# esp_console.net
KiCad netlist of a schematic drawn in EAGLE
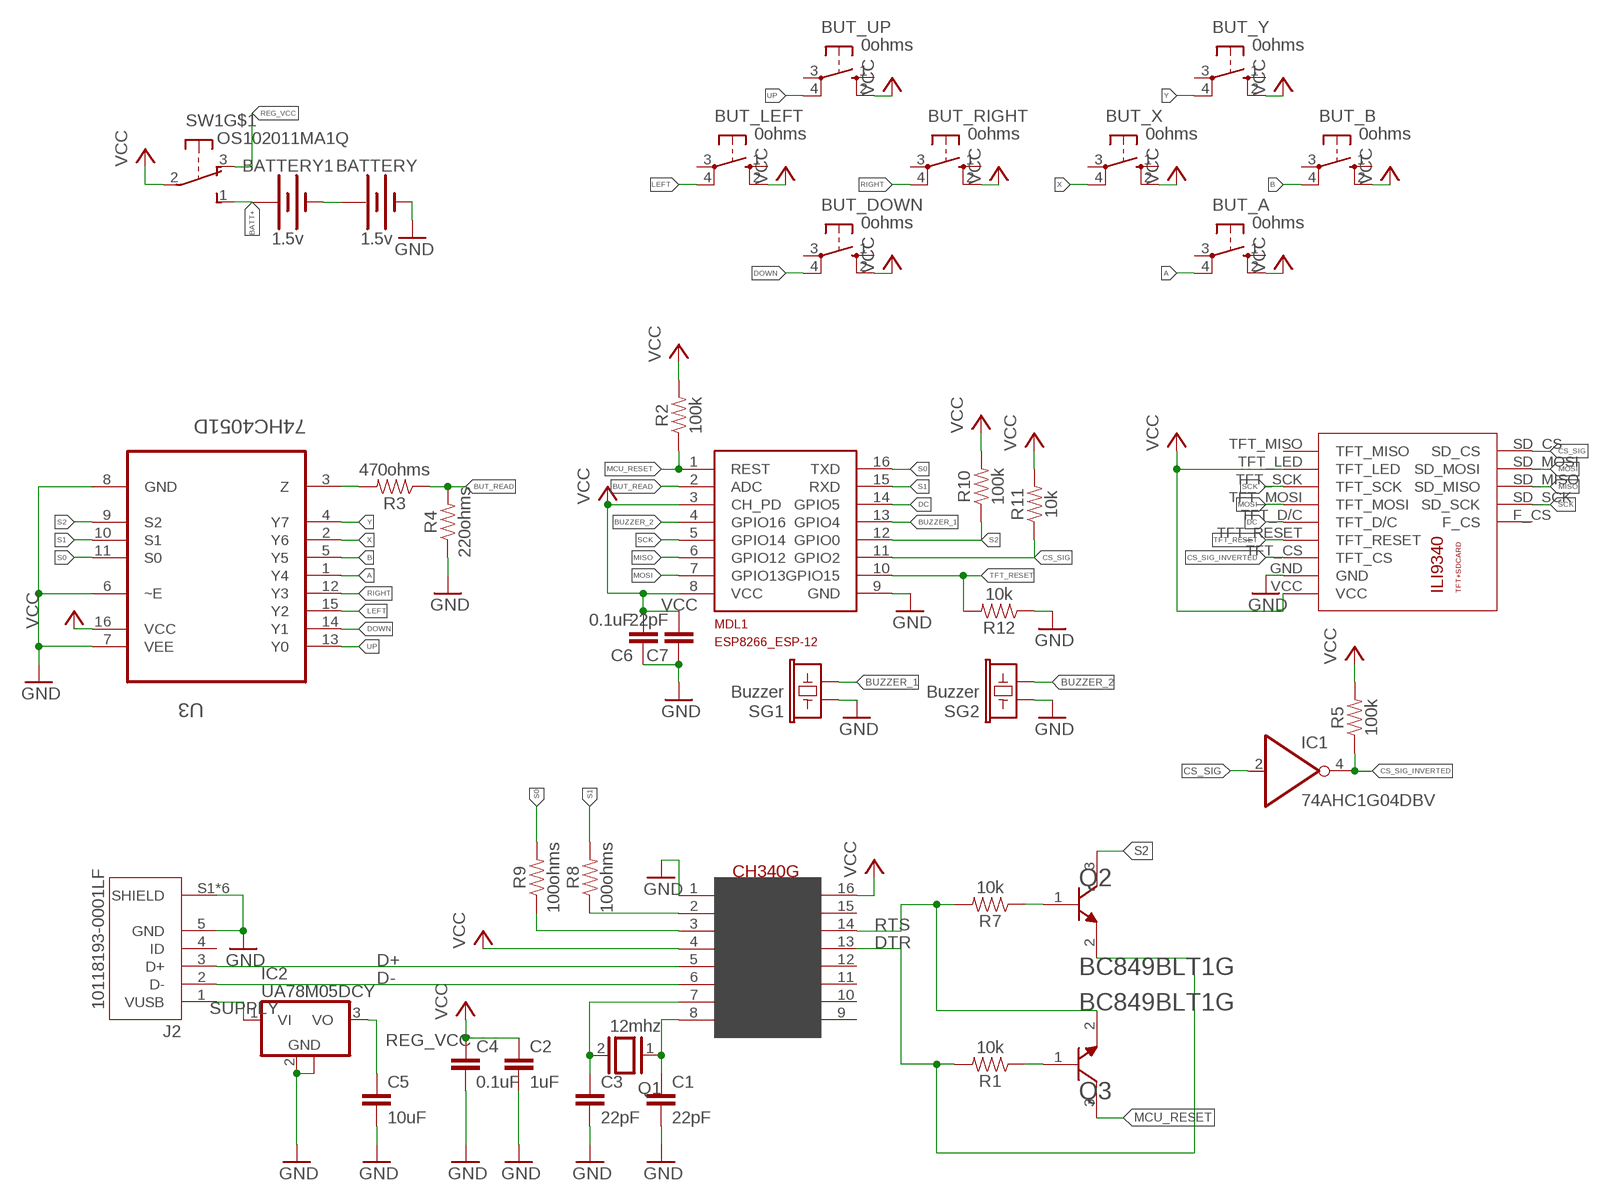
[diagram p0: schematic, sheet 1]

(export (version "E")
  (design (tool "Eeschema 10.0.6"))
  (components
    (comp (ref "BATTERY")
      (value "1.5v")
      (footprint "eagle-import:BATTERY-AA")
      (libsource (lib "eagle-import") (part "BATTERY-AA"))
    )
    (comp (ref "BATTERY1")
      (value "1.5v")
      (footprint "eagle-import:BATTERY-AA")
      (libsource (lib "eagle-import") (part "BATTERY-AA"))
    )
    (comp (ref "BUT_A")
      (value "0ohms")
      (footprint "eagle-import:B3F-10XX")
      (fields (field (name "MPN") "B3F-1000"))
      (libsource (lib "eagle-import") (part "10-XX"))
    )
    (comp (ref "BUT_B")
      (value "0ohms")
      (footprint "eagle-import:B3F-10XX")
      (fields (field (name "MPN") "B3F-1000"))
      (libsource (lib "eagle-import") (part "10-XX"))
    )
    (comp (ref "BUT_DOWN")
      (value "0ohms")
      (footprint "eagle-import:B3F-10XX")
      (fields (field (name "MPN") "B3F-1000"))
      (libsource (lib "eagle-import") (part "10-XX"))
    )
    (comp (ref "BUT_LEFT")
      (value "0ohms")
      (footprint "eagle-import:B3F-10XX")
      (fields (field (name "MPN") "B3F-1000"))
      (libsource (lib "eagle-import") (part "10-XX"))
    )
    (comp (ref "BUT_RIGHT")
      (value "0ohms")
      (footprint "eagle-import:B3F-10XX")
      (fields (field (name "MPN") "B3F-1000"))
      (libsource (lib "eagle-import") (part "10-XX"))
    )
    (comp (ref "BUT_UP")
      (value "0ohms")
      (footprint "eagle-import:B3F-10XX")
      (fields (field (name "MPN") "B3F-1000"))
      (libsource (lib "eagle-import") (part "10-XX"))
    )
    (comp (ref "BUT_X")
      (value "0ohms")
      (footprint "eagle-import:B3F-10XX")
      (fields (field (name "MPN") "B3F-1000"))
      (libsource (lib "eagle-import") (part "10-XX"))
    )
    (comp (ref "BUT_Y")
      (value "0ohms")
      (footprint "eagle-import:B3F-10XX")
      (fields (field (name "MPN") "B3F-1000"))
      (libsource (lib "eagle-import") (part "10-XX"))
    )
    (comp (ref "C1")
      (value "22pF")
      (footprint "eagle-import:C0603")
      (libsource (lib "eagle-import") (part "C-EUC0603"))
    )
    (comp (ref "C2")
      (value "1uF")
      (footprint "eagle-import:C0603")
      (libsource (lib "eagle-import") (part "C-EUC0603"))
    )
    (comp (ref "C3")
      (value "22pF")
      (footprint "eagle-import:C0603")
      (libsource (lib "eagle-import") (part "C-EUC0603"))
    )
    (comp (ref "C4")
      (value "0.1uF")
      (footprint "eagle-import:C0603")
      (libsource (lib "eagle-import") (part "C-EUC0603"))
    )
    (comp (ref "C5")
      (value "10uF")
      (footprint "eagle-import:C0603")
      (libsource (lib "eagle-import") (part "C-EUC0603"))
    )
    (comp (ref "C6")
      (value "0.1uF")
      (footprint "eagle-import:C0603")
      (libsource (lib "eagle-import") (part "C-EUC0603"))
    )
    (comp (ref "C7")
      (value "22pF")
      (footprint "eagle-import:C0603")
      (libsource (lib "eagle-import") (part "C-EUC0603"))
    )
    (comp (ref "IC1")
      (value "74AHC1G04DBV")
      (footprint "eagle-import:SOT23-5")
      (libsource (lib "eagle-import") (part "741G04DBVAHC"))
    )
    (comp (ref "IC2")
      (value "UA78M05DCY")
      (footprint "eagle-import:SOT223")
      (libsource (lib "eagle-import") (part "UA78MDCY05"))
    )
    (comp (ref "J2")
      (value "10118193-0001LF")
      (footprint "eagle-import:FCI_10118193-0001LF")
      (fields (field (name "MF") "Amphenol FCI"))
      (libsource (lib "eagle-import") (part "10118193-0001LF"))
    )
    (comp (ref "MDL1")
      (value "MCU")
      (footprint "eagle-import:ESP8266-ESP12")
      (libsource (lib "eagle-import") (part "ESP8266-12GPIO04/05_CORRECTED"))
    )
    (comp (ref "Q1")
      (value "12mhz")
      (footprint "eagle-import:QS")
      (libsource (lib "eagle-import") (part "XTAL/S"))
    )
    (comp (ref "Q2")
      (value "ON_SEMICONDUCTOR_BC849BLT1GON_SEMICONDUCTOR_BC849BLT1G_0_0")
      (footprint "eagle-import:ON_SEMICONDUCTOR_BC849BLT1G_0")
      (fields (field (name "MF") "On Semiconductor") (field (name "MPN") "BC849BLT1G"))
      (libsource (lib "eagle-import") (part "ON_SEMICONDUCTOR_BC849BLT1GON_SEMICONDUCTOR_BC849BLT1G_0_0"))
    )
    (comp (ref "Q3")
      (value "ON_SEMICONDUCTOR_BC849BLT1GON_SEMICONDUCTOR_BC849BLT1G_0_0")
      (footprint "eagle-import:ON_SEMICONDUCTOR_BC849BLT1G_0")
      (fields (field (name "MF") "On Semiconductor") (field (name "MPN") "BC849BLT1G"))
      (libsource (lib "eagle-import") (part "ON_SEMICONDUCTOR_BC849BLT1GON_SEMICONDUCTOR_BC849BLT1G_0_0"))
    )
    (comp (ref "R1")
      (value "10k")
      (footprint "eagle-import:0603")
      (libsource (lib "eagle-import") (part "10KOHM-0603-1/10W-1%"))
    )
    (comp (ref "R2")
      (value "100k")
      (footprint "eagle-import:0603")
      (libsource (lib "eagle-import") (part "10KOHM-0603-1/10W-1%"))
    )
    (comp (ref "R3")
      (value "470ohms")
      (footprint "eagle-import:0603")
      (libsource (lib "eagle-import") (part "10KOHM-0603-1/10W-1%"))
    )
    (comp (ref "R4")
      (value "220ohms")
      (footprint "eagle-import:0603")
      (libsource (lib "eagle-import") (part "10KOHM-0603-1/10W-1%"))
    )
    (comp (ref "R5")
      (value "100k")
      (footprint "eagle-import:0603")
      (libsource (lib "eagle-import") (part "10KOHM-0603-1/10W-1%"))
    )
    (comp (ref "R7")
      (value "10k")
      (footprint "eagle-import:0603")
      (libsource (lib "eagle-import") (part "10KOHM-0603-1/10W-1%"))
    )
    (comp (ref "R8")
      (value "100ohms")
      (footprint "eagle-import:0603")
      (libsource (lib "eagle-import") (part "10KOHM-0603-1/10W-1%"))
    )
    (comp (ref "R9")
      (value "100ohms")
      (footprint "eagle-import:0603")
      (libsource (lib "eagle-import") (part "10KOHM-0603-1/10W-1%"))
    )
    (comp (ref "R10")
      (value "100k")
      (footprint "eagle-import:0603")
      (libsource (lib "eagle-import") (part "10KOHM-0603-1/10W-1%"))
    )
    (comp (ref "R11")
      (value "10k")
      (footprint "eagle-import:0603")
      (libsource (lib "eagle-import") (part "10KOHM-0603-1/10W-1%"))
    )
    (comp (ref "R12")
      (value "10k")
      (footprint "eagle-import:0603")
      (libsource (lib "eagle-import") (part "10KOHM-0603-1/10W-1%"))
    )
    (comp (ref "SG1")
      (value "Buzzer")
      (footprint "eagle-import:BUZZER-CCV")
      (libsource (lib "eagle-import") (part "BUZZERSMD2"))
    )
    (comp (ref "SG2")
      (value "Buzzer")
      (footprint "eagle-import:BUZZER-CCV")
      (libsource (lib "eagle-import") (part "BUZZERSMD2"))
    )
    (comp (ref "SW1")
      (value "OS102011MA1Q")
      (footprint "eagle-import:OS102011MA1Q")
      (libsource (lib "eagle-import") (part "OS102011MA1Q"))
    )
    (comp (ref "U$1")
      (value "CH340G")
      (footprint "eagle-import:SOIC16")
      (libsource (lib "eagle-import") (part "CH340G"))
    )
    (comp (ref "U$2")
      (value "ILI9340-5PIN")
      (footprint "eagle-import:ILI9340-5PIN")
      (libsource (lib "eagle-import") (part "ILI9340-5PIN"))
    )
    (comp (ref "U3")
      (value "74HC4051D")
      (footprint "eagle-import:SOIC127P600X175-16N")
      (libsource (lib "eagle-import") (part "74HC4051D"))
    )
  )
  (nets
    (net (code "1") (name "/D+") (class "Default")
      (node (ref "J2") (pin "3") (pinfunction "D+_3") (pintype "passive"))
      (node (ref "U$1") (pin "5") (pinfunction "D+_5") (pintype "bidirectional"))
    )
    (net (code "2") (name "/D-") (class "Default")
      (node (ref "J2") (pin "2") (pinfunction "D-_2") (pintype "passive"))
      (node (ref "U$1") (pin "6") (pinfunction "D-_6") (pintype "bidirectional"))
    )
    (net (code "3") (name "/DTR") (class "Default")
      (node (ref "Q2") (pin "2") (pinfunction "E_2") (pintype "passive"))
      (node (ref "R1") (pin "2") (pinfunction "2_2") (pintype "passive"))
      (node (ref "U$1") (pin "13") (pinfunction "DTR_13") (pintype "bidirectional"))
    )
    (net (code "4") (name "/RTS") (class "Default")
      (node (ref "Q3") (pin "2") (pinfunction "E_2") (pintype "passive"))
      (node (ref "R7") (pin "2") (pinfunction "2_2") (pintype "passive"))
      (node (ref "U$1") (pin "14") (pinfunction "RTS_14") (pintype "bidirectional"))
    )
    (net (code "5") (name "/SUPPLY") (class "Default")
      (node (ref "IC2") (pin "1") (pinfunction "VI_1") (pintype "input"))
      (node (ref "J2") (pin "1") (pinfunction "VUSB_1") (pintype "passive"))
    )
    (net (code "6") (name "A") (class "Default")
      (node (ref "BUT_A") (pin "4") (pinfunction "P1_4") (pintype "passive"))
      (node (ref "U3") (pin "1") (pinfunction "Y4_1") (pintype "bidirectional"))
    )
    (net (code "7") (name "B") (class "Default")
      (node (ref "BUT_B") (pin "4") (pinfunction "P1_4") (pintype "passive"))
      (node (ref "U3") (pin "5") (pinfunction "Y5_5") (pintype "bidirectional"))
    )
    (net (code "8") (name "BATT+") (class "Default")
      (node (ref "BATTERY1") (pin "PWR@1") (pinfunction "+_PWR@1") (pintype "power_in"))
      (node (ref "SW1") (pin "1") (pinfunction "S_1") (pintype "passive"))
    )
    (net (code "9") (name "BUT_READ") (class "Default")
      (node (ref "MDL1") (pin "2") (pinfunction "ADC_2") (pintype "bidirectional"))
      (node (ref "R3") (pin "1") (pinfunction "1_1") (pintype "passive"))
      (node (ref "R4") (pin "2") (pinfunction "2_2") (pintype "passive"))
    )
    (net (code "10") (name "BUZZER_1") (class "Default")
      (node (ref "MDL1") (pin "13") (pinfunction "GPIO4_13") (pintype "bidirectional"))
      (node (ref "SG1") (pin "-") (pinfunction "2_-") (pintype "passive"))
    )
    (net (code "11") (name "BUZZER_2") (class "Default")
      (node (ref "MDL1") (pin "4") (pinfunction "GPIO16_4") (pintype "bidirectional"))
      (node (ref "SG2") (pin "-") (pinfunction "2_-") (pintype "passive"))
    )
    (net (code "12") (name "CS_SIG") (class "Default")
      (node (ref "IC1") (pin "2") (pinfunction "I_2") (pintype "input"))
      (node (ref "MDL1") (pin "11") (pinfunction "GPIO2_11") (pintype "bidirectional"))
      (node (ref "R11") (pin "1") (pinfunction "1_1") (pintype "passive"))
      (node (ref "U$2") (pin "SD_CS") (pinfunction "SD_CS_SD_CS") (pintype "input"))
    )
    (net (code "13") (name "CS_SIG_INVERTED") (class "Default")
      (node (ref "IC1") (pin "4") (pinfunction "O_4") (pintype "output"))
      (node (ref "R5") (pin "1") (pinfunction "1_1") (pintype "passive"))
      (node (ref "U$2") (pin "TFT_CS") (pinfunction "TFT_CS_TFT_CS") (pintype "input"))
    )
    (net (code "14") (name "DC") (class "Default")
      (node (ref "MDL1") (pin "14") (pinfunction "GPIO5_14") (pintype "bidirectional"))
      (node (ref "U$2") (pin "TFT_D/C") (pinfunction "TFT_D/C_TFT_D/C") (pintype "input"))
    )
    (net (code "15") (name "DOWN") (class "Default")
      (node (ref "BUT_DOWN") (pin "4") (pinfunction "P1_4") (pintype "passive"))
      (node (ref "U3") (pin "14") (pinfunction "Y1_14") (pintype "bidirectional"))
    )
    (net (code "16") (name "GND") (class "Default")
      (node (ref "BATTERY") (pin "GND@1") (pinfunction "-_GND@1") (pintype "power_in"))
      (node (ref "C1") (pin "2") (pinfunction "2_2") (pintype "passive"))
      (node (ref "C2") (pin "2") (pinfunction "2_2") (pintype "passive"))
      (node (ref "C3") (pin "2") (pinfunction "2_2") (pintype "passive"))
      (node (ref "C4") (pin "2") (pinfunction "2_2") (pintype "passive"))
      (node (ref "C5") (pin "2") (pinfunction "2_2") (pintype "passive"))
      (node (ref "C6") (pin "1") (pinfunction "1_1") (pintype "passive"))
      (node (ref "C7") (pin "1") (pinfunction "1_1") (pintype "passive"))
      (node (ref "IC2") (pin "2") (pinfunction "GND_2") (pintype "passive"))
      (node (ref "IC2") (pin "4") (pinfunction "GND_4") (pintype "passive"))
      (node (ref "J2") (pin "5") (pinfunction "GND_5") (pintype "passive"))
      (node (ref "J2") (pin "S1") (pinfunction "SHIELD_S1") (pintype "passive"))
      (node (ref "J2") (pin "S2") (pinfunction "SHIELD_S2") (pintype "passive"))
      (node (ref "J2") (pin "S3") (pinfunction "SHIELD_S3") (pintype "passive"))
      (node (ref "J2") (pin "S4") (pinfunction "SHIELD_S4") (pintype "passive"))
      (node (ref "J2") (pin "S5") (pinfunction "SHIELD_S5") (pintype "passive"))
      (node (ref "J2") (pin "S6") (pinfunction "SHIELD_S6") (pintype "passive"))
      (node (ref "MDL1") (pin "9") (pinfunction "GND_9") (pintype "bidirectional"))
      (node (ref "R12") (pin "1") (pinfunction "1_1") (pintype "passive"))
      (node (ref "R4") (pin "1") (pinfunction "1_1") (pintype "passive"))
      (node (ref "SG1") (pin "+") (pinfunction "1_+") (pintype "passive"))
      (node (ref "SG2") (pin "+") (pinfunction "1_+") (pintype "passive"))
      (node (ref "U$1") (pin "1") (pinfunction "GND_1") (pintype "bidirectional"))
      (node (ref "U$2") (pin "GND") (pinfunction "GND_GND") (pintype "power_in"))
      (node (ref "U3") (pin "6") (pinfunction "~{E}_6") (pintype "input"))
      (node (ref "U3") (pin "7") (pinfunction "VEE_7") (pintype "power_in"))
      (node (ref "U3") (pin "8") (pinfunction "GND_8") (pintype "passive"))
    )
    (net (code "17") (name "LEFT") (class "Default")
      (node (ref "BUT_LEFT") (pin "4") (pinfunction "P1_4") (pintype "passive"))
      (node (ref "U3") (pin "15") (pinfunction "Y2_15") (pintype "bidirectional"))
    )
    (net (code "18") (name "MCU_RESET") (class "Default")
      (node (ref "MDL1") (pin "1") (pinfunction "REST_1") (pintype "bidirectional"))
      (node (ref "Q3") (pin "3") (pinfunction "C_3") (pintype "passive"))
      (node (ref "R2") (pin "1") (pinfunction "1_1") (pintype "passive"))
    )
    (net (code "19") (name "MISO") (class "Default")
      (node (ref "MDL1") (pin "6") (pinfunction "GPIO12_6") (pintype "bidirectional"))
      (node (ref "U$2") (pin "SD_MISO") (pinfunction "SD_MISO_SD_MISO") (pintype "output"))
    )
    (net (code "20") (name "MOSI") (class "Default")
      (node (ref "MDL1") (pin "7") (pinfunction "GPIO13_7") (pintype "bidirectional"))
      (node (ref "U$2") (pin "SD_MOSI") (pinfunction "SD_MOSI_SD_MOSI") (pintype "input"))
      (node (ref "U$2") (pin "TFT_MOSI") (pinfunction "TFT_MOSI_TFT_MOSI") (pintype "input"))
    )
    (net (code "21") (name "Net-(BATTERY-+)") (class "Default")
      (node (ref "BATTERY") (pin "PWR@1") (pinfunction "+_PWR@1") (pintype "power_in"))
      (node (ref "BATTERY1") (pin "GND@1") (pinfunction "-_GND@1") (pintype "power_in"))
    )
    (net (code "22") (name "Net-(Q2-B)") (class "Default")
      (node (ref "Q2") (pin "1") (pinfunction "B_1") (pintype "passive"))
      (node (ref "R7") (pin "1") (pinfunction "1_1") (pintype "passive"))
    )
    (net (code "23") (name "Net-(Q3-B)") (class "Default")
      (node (ref "Q3") (pin "1") (pinfunction "B_1") (pintype "passive"))
      (node (ref "R1") (pin "1") (pinfunction "1_1") (pintype "passive"))
    )
    (net (code "24") (name "Net-(U$1-RX)") (class "Default")
      (node (ref "R9") (pin "1") (pinfunction "1_1") (pintype "passive"))
      (node (ref "U$1") (pin "3") (pinfunction "RX_3") (pintype "bidirectional"))
    )
    (net (code "25") (name "Net-(U$1-TX)") (class "Default")
      (node (ref "R8") (pin "1") (pinfunction "1_1") (pintype "passive"))
      (node (ref "U$1") (pin "2") (pinfunction "TX_2") (pintype "bidirectional"))
    )
    (net (code "26") (name "Net-(U$1-XI)") (class "Default")
      (node (ref "C3") (pin "1") (pinfunction "1_1") (pintype "passive"))
      (node (ref "Q1") (pin "2") (pinfunction "2_2") (pintype "passive"))
      (node (ref "U$1") (pin "7") (pinfunction "XI_7") (pintype "bidirectional"))
    )
    (net (code "27") (name "Net-(U$1-XO)") (class "Default")
      (node (ref "C1") (pin "1") (pinfunction "1_1") (pintype "passive"))
      (node (ref "Q1") (pin "1") (pinfunction "1_1") (pintype "passive"))
      (node (ref "U$1") (pin "8") (pinfunction "XO_8") (pintype "bidirectional"))
    )
    (net (code "28") (name "Net-(U3-Z)") (class "Default")
      (node (ref "R3") (pin "2") (pinfunction "2_2") (pintype "passive"))
      (node (ref "U3") (pin "3") (pinfunction "Z_3") (pintype "bidirectional"))
    )
    (net (code "29") (name "REG_VCC") (class "Default")
      (node (ref "C5") (pin "1") (pinfunction "1_1") (pintype "passive"))
      (node (ref "IC2") (pin "3") (pinfunction "VO_3") (pintype "passive"))
      (node (ref "SW1") (pin "3") (pinfunction "O_3") (pintype "passive"))
    )
    (net (code "30") (name "RIGHT") (class "Default")
      (node (ref "BUT_RIGHT") (pin "4") (pinfunction "P1_4") (pintype "passive"))
      (node (ref "U3") (pin "12") (pinfunction "Y3_12") (pintype "bidirectional"))
    )
    (net (code "31") (name "S0") (class "Default")
      (node (ref "MDL1") (pin "16") (pinfunction "TXD_16") (pintype "bidirectional"))
      (node (ref "R9") (pin "2") (pinfunction "2_2") (pintype "passive"))
      (node (ref "U3") (pin "11") (pinfunction "S0_11") (pintype "input"))
    )
    (net (code "32") (name "S1") (class "Default")
      (node (ref "MDL1") (pin "15") (pinfunction "RXD_15") (pintype "bidirectional"))
      (node (ref "R8") (pin "2") (pinfunction "2_2") (pintype "passive"))
      (node (ref "U3") (pin "10") (pinfunction "S1_10") (pintype "input"))
    )
    (net (code "33") (name "S2") (class "Default")
      (node (ref "MDL1") (pin "12") (pinfunction "GPIO0_12") (pintype "bidirectional"))
      (node (ref "Q2") (pin "3") (pinfunction "C_3") (pintype "passive"))
      (node (ref "R10") (pin "1") (pinfunction "1_1") (pintype "passive"))
      (node (ref "U3") (pin "9") (pinfunction "S2_9") (pintype "input"))
    )
    (net (code "34") (name "SCK") (class "Default")
      (node (ref "MDL1") (pin "5") (pinfunction "GPIO14_5") (pintype "bidirectional"))
      (node (ref "U$2") (pin "SD_SCK") (pinfunction "SD_SCK_SD_SCK") (pintype "input"))
      (node (ref "U$2") (pin "TFT_SCK") (pinfunction "TFT_SCK_TFT_SCK") (pintype "input"))
    )
    (net (code "35") (name "TFT_RESET") (class "Default")
      (node (ref "MDL1") (pin "10") (pinfunction "GPIO15_10") (pintype "bidirectional"))
      (node (ref "R12") (pin "2") (pinfunction "2_2") (pintype "passive"))
      (node (ref "U$2") (pin "TFT_RESET") (pinfunction "TFT_RESET_TFT_RESET") (pintype "input"))
    )
    (net (code "36") (name "UP") (class "Default")
      (node (ref "BUT_UP") (pin "4") (pinfunction "P1_4") (pintype "passive"))
      (node (ref "U3") (pin "13") (pinfunction "Y0_13") (pintype "bidirectional"))
    )
    (net (code "37") (name "VCC") (class "Default")
      (node (ref "BUT_A") (pin "2") (pinfunction "S1_2") (pintype "passive"))
      (node (ref "BUT_B") (pin "2") (pinfunction "S1_2") (pintype "passive"))
      (node (ref "BUT_DOWN") (pin "2") (pinfunction "S1_2") (pintype "passive"))
      (node (ref "BUT_LEFT") (pin "2") (pinfunction "S1_2") (pintype "passive"))
      (node (ref "BUT_RIGHT") (pin "2") (pinfunction "S1_2") (pintype "passive"))
      (node (ref "BUT_UP") (pin "2") (pinfunction "S1_2") (pintype "passive"))
      (node (ref "BUT_X") (pin "2") (pinfunction "S1_2") (pintype "passive"))
      (node (ref "BUT_Y") (pin "2") (pinfunction "S1_2") (pintype "passive"))
      (node (ref "C2") (pin "1") (pinfunction "1_1") (pintype "passive"))
      (node (ref "C4") (pin "1") (pinfunction "1_1") (pintype "passive"))
      (node (ref "C6") (pin "2") (pinfunction "2_2") (pintype "passive"))
      (node (ref "C7") (pin "2") (pinfunction "2_2") (pintype "passive"))
      (node (ref "MDL1") (pin "3") (pinfunction "CH_PD_3") (pintype "bidirectional"))
      (node (ref "MDL1") (pin "8") (pinfunction "VCC_8") (pintype "bidirectional"))
      (node (ref "R10") (pin "2") (pinfunction "2_2") (pintype "passive"))
      (node (ref "R11") (pin "2") (pinfunction "2_2") (pintype "passive"))
      (node (ref "R2") (pin "2") (pinfunction "2_2") (pintype "passive"))
      (node (ref "R5") (pin "2") (pinfunction "2_2") (pintype "passive"))
      (node (ref "SW1") (pin "2") (pinfunction "P_2") (pintype "passive"))
      (node (ref "U$1") (pin "16") (pinfunction "VCC_16") (pintype "bidirectional"))
      (node (ref "U$1") (pin "4") (pinfunction "V3_4") (pintype "bidirectional"))
      (node (ref "U$2") (pin "TFT_LED") (pinfunction "TFT_LED_TFT_LED") (pintype "power_in"))
      (node (ref "U$2") (pin "VCC") (pinfunction "VCC_VCC") (pintype "power_in"))
      (node (ref "U3") (pin "16") (pinfunction "VCC_16") (pintype "power_in"))
    )
    (net (code "38") (name "X") (class "Default")
      (node (ref "BUT_X") (pin "4") (pinfunction "P1_4") (pintype "passive"))
      (node (ref "U3") (pin "2") (pinfunction "Y6_2") (pintype "bidirectional"))
    )
    (net (code "39") (name "Y") (class "Default")
      (node (ref "BUT_Y") (pin "4") (pinfunction "P1_4") (pintype "passive"))
      (node (ref "U3") (pin "4") (pinfunction "Y7_4") (pintype "bidirectional"))
    )
    (net (code "40") (name "unconnected-(BUT_A-P-Pad3)") (class "Default")
      (node (ref "BUT_A") (pin "3") (pinfunction "P_3") (pintype "passive"))
    )
    (net (code "41") (name "unconnected-(BUT_A-S-Pad1)") (class "Default")
      (node (ref "BUT_A") (pin "1") (pinfunction "S_1") (pintype "passive"))
    )
    (net (code "42") (name "unconnected-(BUT_B-P-Pad3)") (class "Default")
      (node (ref "BUT_B") (pin "3") (pinfunction "P_3") (pintype "passive"))
    )
    (net (code "43") (name "unconnected-(BUT_B-S-Pad1)") (class "Default")
      (node (ref "BUT_B") (pin "1") (pinfunction "S_1") (pintype "passive"))
    )
    (net (code "44") (name "unconnected-(BUT_DOWN-P-Pad3)") (class "Default")
      (node (ref "BUT_DOWN") (pin "3") (pinfunction "P_3") (pintype "passive"))
    )
    (net (code "45") (name "unconnected-(BUT_DOWN-S-Pad1)") (class "Default")
      (node (ref "BUT_DOWN") (pin "1") (pinfunction "S_1") (pintype "passive"))
    )
    (net (code "46") (name "unconnected-(BUT_LEFT-P-Pad3)") (class "Default")
      (node (ref "BUT_LEFT") (pin "3") (pinfunction "P_3") (pintype "passive"))
    )
    (net (code "47") (name "unconnected-(BUT_LEFT-S-Pad1)") (class "Default")
      (node (ref "BUT_LEFT") (pin "1") (pinfunction "S_1") (pintype "passive"))
    )
    (net (code "48") (name "unconnected-(BUT_RIGHT-P-Pad3)") (class "Default")
      (node (ref "BUT_RIGHT") (pin "3") (pinfunction "P_3") (pintype "passive"))
    )
    (net (code "49") (name "unconnected-(BUT_RIGHT-S-Pad1)") (class "Default")
      (node (ref "BUT_RIGHT") (pin "1") (pinfunction "S_1") (pintype "passive"))
    )
    (net (code "50") (name "unconnected-(BUT_UP-P-Pad3)") (class "Default")
      (node (ref "BUT_UP") (pin "3") (pinfunction "P_3") (pintype "passive"))
    )
    (net (code "51") (name "unconnected-(BUT_UP-S-Pad1)") (class "Default")
      (node (ref "BUT_UP") (pin "1") (pinfunction "S_1") (pintype "passive"))
    )
    (net (code "52") (name "unconnected-(BUT_X-P-Pad3)") (class "Default")
      (node (ref "BUT_X") (pin "3") (pinfunction "P_3") (pintype "passive"))
    )
    (net (code "53") (name "unconnected-(BUT_X-S-Pad1)") (class "Default")
      (node (ref "BUT_X") (pin "1") (pinfunction "S_1") (pintype "passive"))
    )
    (net (code "54") (name "unconnected-(BUT_Y-P-Pad3)") (class "Default")
      (node (ref "BUT_Y") (pin "3") (pinfunction "P_3") (pintype "passive"))
    )
    (net (code "55") (name "unconnected-(BUT_Y-S-Pad1)") (class "Default")
      (node (ref "BUT_Y") (pin "1") (pinfunction "S_1") (pintype "passive"))
    )
    (net (code "56") (name "unconnected-(J2-ID-Pad4)") (class "Default")
      (node (ref "J2") (pin "4") (pinfunction "ID_4") (pintype "passive"))
    )
    (net (code "57") (name "unconnected-(U$1-CTS-Pad9)") (class "Default")
      (node (ref "U$1") (pin "9") (pinfunction "CTS_9") (pintype "bidirectional"))
    )
    (net (code "58") (name "unconnected-(U$1-DCD-Pad12)") (class "Default")
      (node (ref "U$1") (pin "12") (pinfunction "DCD_12") (pintype "bidirectional"))
    )
    (net (code "59") (name "unconnected-(U$1-DSR-Pad10)") (class "Default")
      (node (ref "U$1") (pin "10") (pinfunction "DSR_10") (pintype "bidirectional"))
    )
    (net (code "60") (name "unconnected-(U$1-RI-Pad11)") (class "Default")
      (node (ref "U$1") (pin "11") (pinfunction "RI_11") (pintype "bidirectional"))
    )
    (net (code "61") (name "unconnected-(U$1-RS232-Pad15)") (class "Default")
      (node (ref "U$1") (pin "15") (pinfunction "RS232_15") (pintype "bidirectional"))
    )
    (net (code "62") (name "unconnected-(U$2-PadF_CS)") (class "Default")
      (node (ref "U$2") (pin "F_CS") (pinfunction "F_CS_F_CS") (pintype "bidirectional"))
    )
    (net (code "63") (name "unconnected-(U$2-PadTFT_MISO)") (class "Default")
      (node (ref "U$2") (pin "TFT_MISO") (pinfunction "TFT_MISO_TFT_MISO") (pintype "no_connect"))
    )
  )
)
